# SCH_nfcCard_2025-11-06.net
KiCad netlist of a schematic drawn in EasyEDA
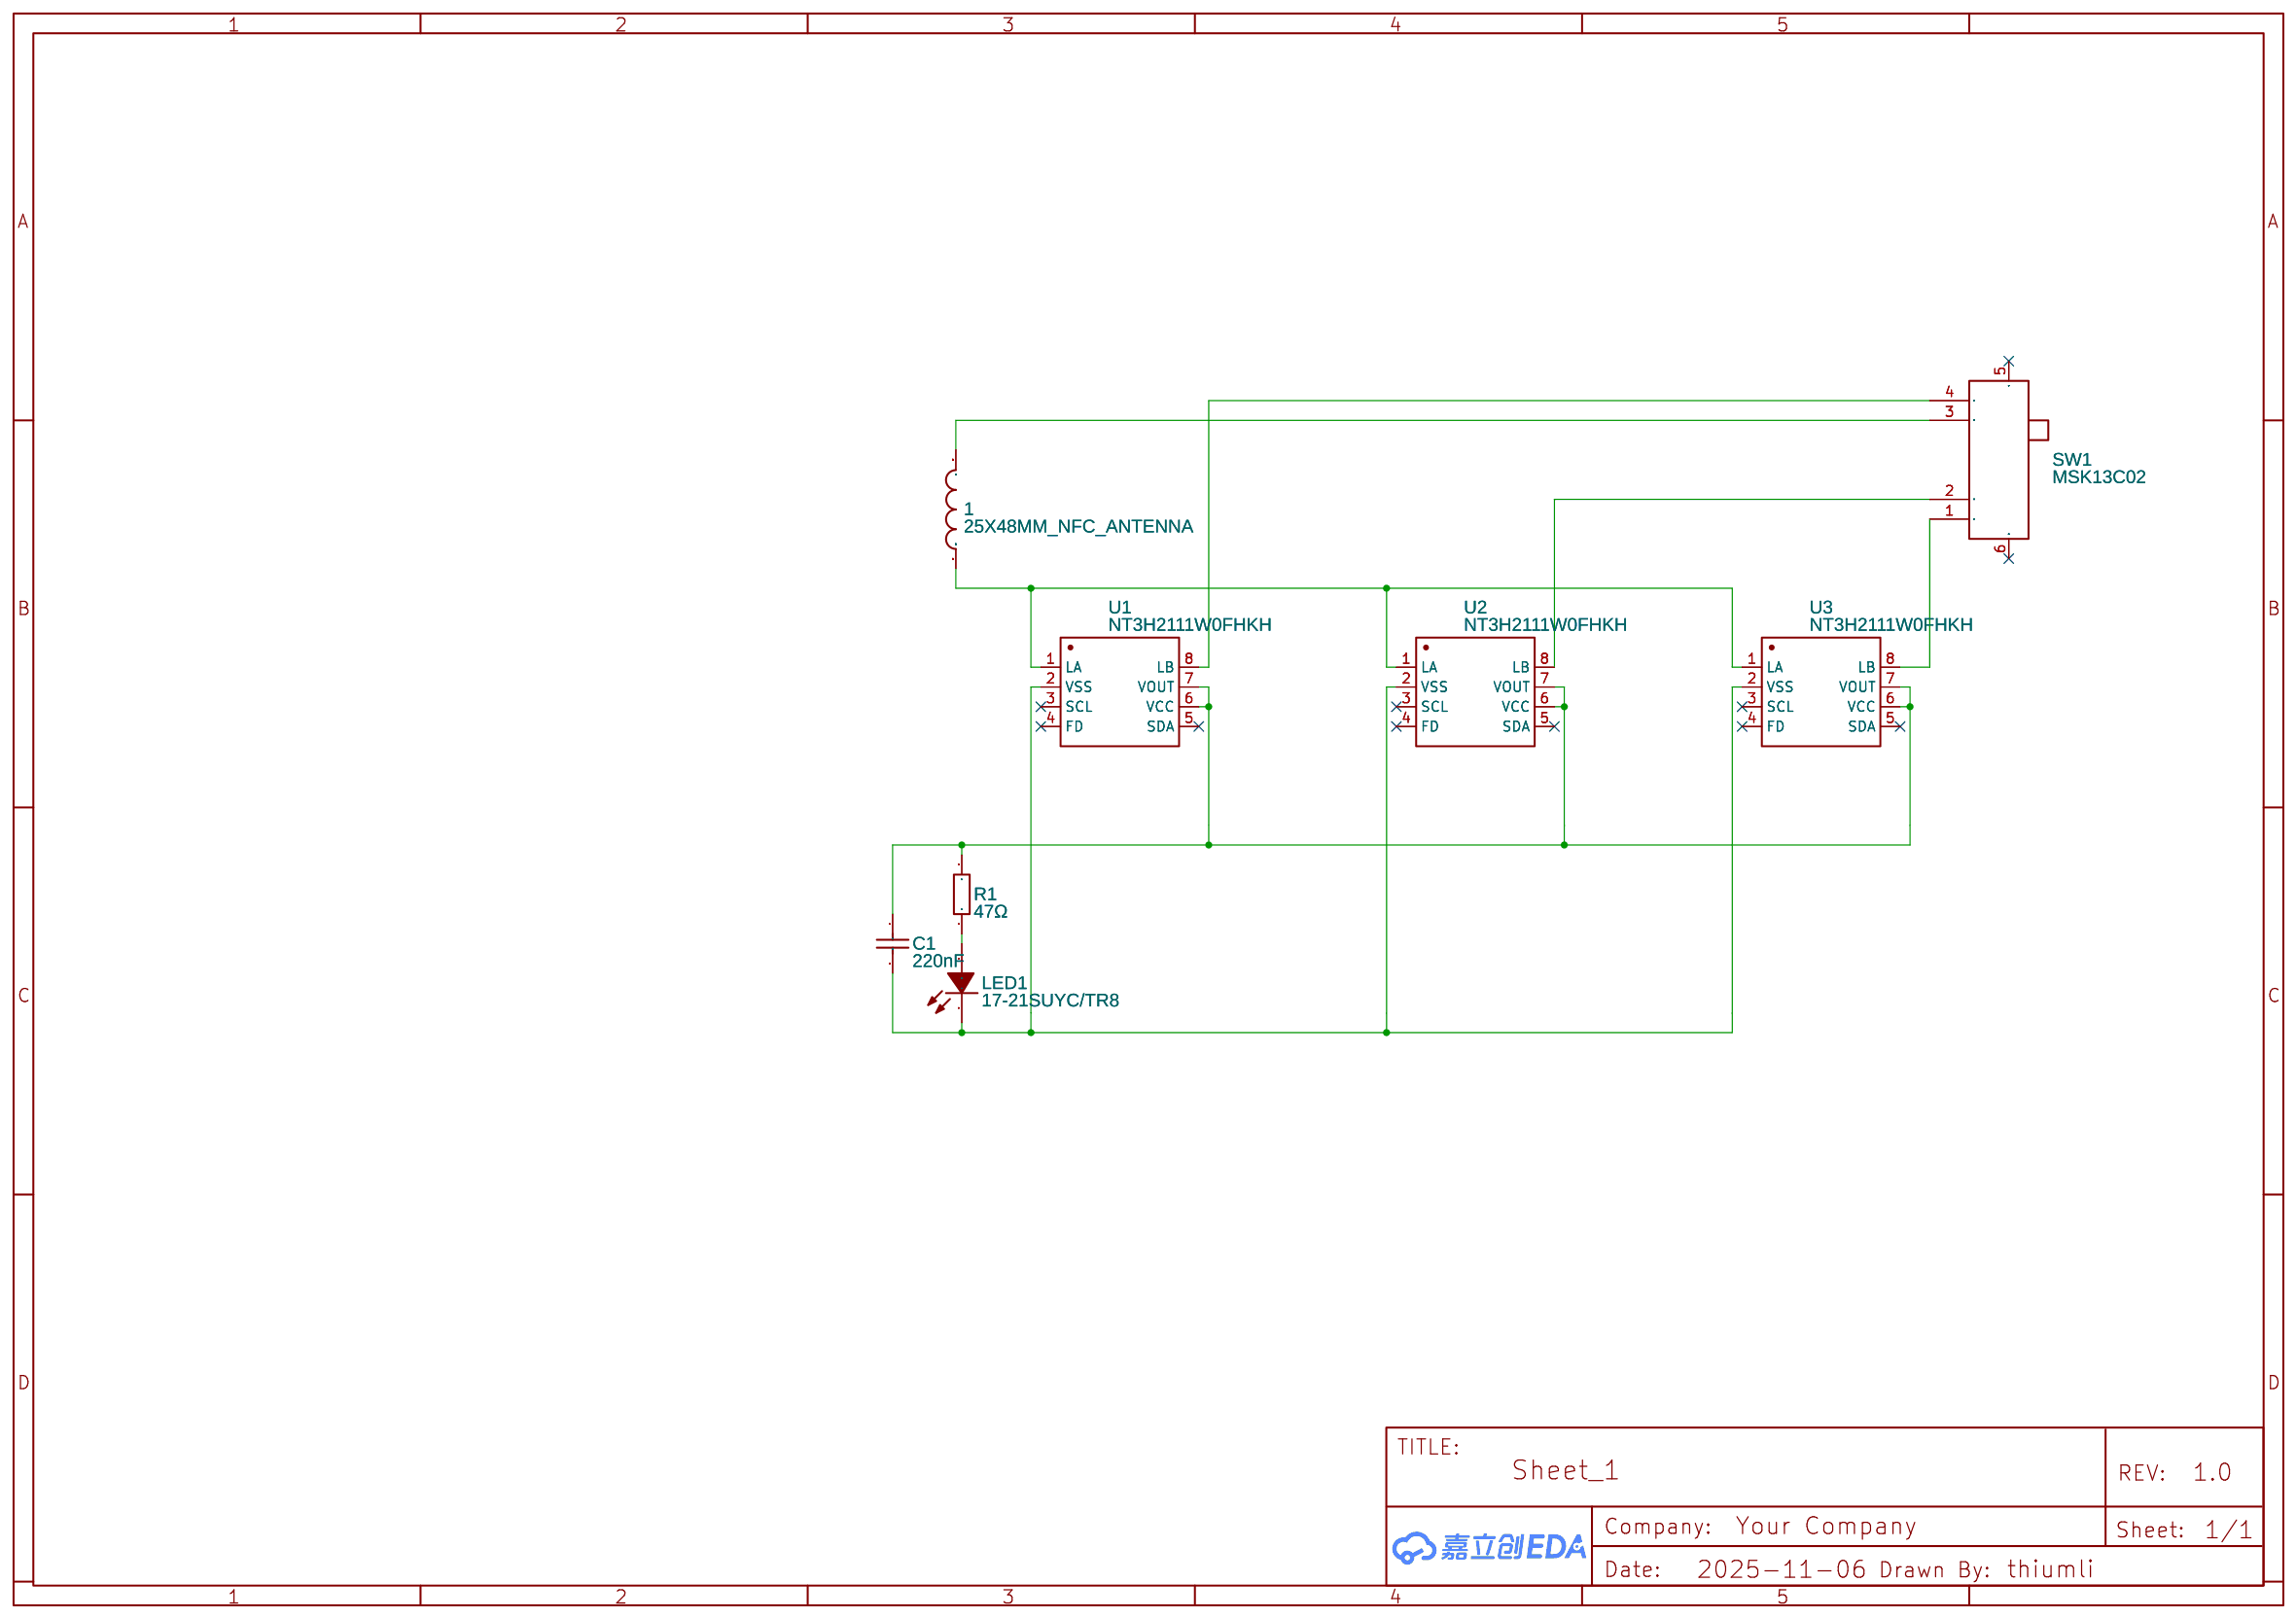
[diagram p0: schematic sheet]

(export (version "E")
  (design (tool "Eeschema 10.0.6"))
  (components
    (comp (ref "1") (value "25X48MM_NFC_ANTENNA") (libsource (lib "") (part "25X48MM_NFC_ANTENNA")))
    (comp (ref "C1")
      (value "220nF")
      (fields
        (field (name "Manufacturer Part") "CL10B224KA8NNNC")
        (field (name "Manufacturer") "SAMSUNG(三星)")
      )
      (libsource (lib "") (part "CL10B224KA8NNNC"))
    )
    (comp (ref "LED1")
      (value "17-21SUYC/TR8")
      (fields (field (name "Manufacturer Part") "KT-0805黄灯") (field (name "Manufacturer") "KENTO"))
      (libsource (lib "") (part "17-21SUYC/TR8"))
    )
    (comp (ref "R1")
      (value "47Ω")
      (fields
        (field (name "Manufacturer Part") "0603WAF470JT5E")
        (field (name "Manufacturer") "UNI-ROYAL(厚声)")
      )
      (libsource (lib "") (part "0603WAF470JT5E"))
    )
    (comp (ref "SW1")
      (value "MSK13C02")
      (fields (field (name "Manufacturer") "SHOU HAN(首韩)"))
      (libsource (lib "") (part "MSK13C02"))
    )
    (comp (ref "U1")
      (value "NT3H2111W0FHKH")
      (fields (field (name "Manufacturer") "NXP(恩智浦)"))
      (libsource (lib "") (part "NT3H2111W0FHKH"))
    )
    (comp (ref "U2")
      (value "NT3H2111W0FHKH")
      (fields (field (name "Manufacturer") "NXP(恩智浦)"))
      (libsource (lib "") (part "NT3H2111W0FHKH"))
    )
    (comp (ref "U3")
      (value "NT3H2111W0FHKH")
      (fields (field (name "Manufacturer") "NXP(恩智浦)"))
      (libsource (lib "") (part "NT3H2111W0FHKH"))
    )
  )
  (nets
    (net (code "1") (name "Net-(1-PadP$2)") (class "Default")
      (node (ref "1") (pin "P$2") (pinfunction "P$2_P$2") (pintype "bidirectional"))
      (node (ref "SW1") (pin "3") (pinfunction "3_3") (pintype "unspecified"))
    )
    (net (code "2") (name "Net-(LED1-+)") (class "Default")
      (node (ref "LED1") (pin "1") (pinfunction "+_1") (pintype "unspecified"))
      (node (ref "R1") (pin "1") (pinfunction "1_1") (pintype "input"))
    )
    (net (code "3") (name "Net-(LED1--)") (class "Default")
      (node (ref "C1") (pin "2") (pinfunction "2_2") (pintype "input"))
      (node (ref "LED1") (pin "2") (pinfunction "-_2") (pintype "unspecified"))
      (node (ref "U1") (pin "2") (pinfunction "VSS_2") (pintype "unspecified"))
      (node (ref "U2") (pin "2") (pinfunction "VSS_2") (pintype "unspecified"))
      (node (ref "U3") (pin "2") (pinfunction "VSS_2") (pintype "unspecified"))
    )
    (net (code "4") (name "Net-(U1-LA)") (class "Default")
      (node (ref "1") (pin "P$1") (pinfunction "P$1_P$1") (pintype "bidirectional"))
      (node (ref "U1") (pin "1") (pinfunction "LA_1") (pintype "unspecified"))
      (node (ref "U2") (pin "1") (pinfunction "LA_1") (pintype "unspecified"))
      (node (ref "U3") (pin "1") (pinfunction "LA_1") (pintype "unspecified"))
    )
    (net (code "5") (name "Net-(U1-LB)") (class "Default")
      (node (ref "SW1") (pin "4") (pinfunction "4_4") (pintype "unspecified"))
      (node (ref "U1") (pin "8") (pinfunction "LB_8") (pintype "unspecified"))
    )
    (net (code "6") (name "Net-(U1-VCC)") (class "Default")
      (node (ref "C1") (pin "1") (pinfunction "1_1") (pintype "input"))
      (node (ref "R1") (pin "2") (pinfunction "2_2") (pintype "input"))
      (node (ref "U1") (pin "6") (pinfunction "VCC_6") (pintype "unspecified"))
      (node (ref "U1") (pin "7") (pinfunction "VOUT_7") (pintype "unspecified"))
      (node (ref "U2") (pin "6") (pinfunction "VCC_6") (pintype "unspecified"))
      (node (ref "U2") (pin "7") (pinfunction "VOUT_7") (pintype "unspecified"))
      (node (ref "U3") (pin "6") (pinfunction "VCC_6") (pintype "unspecified"))
      (node (ref "U3") (pin "7") (pinfunction "VOUT_7") (pintype "unspecified"))
    )
    (net (code "7") (name "Net-(U2-LB)") (class "Default")
      (node (ref "SW1") (pin "2") (pinfunction "2_2") (pintype "unspecified"))
      (node (ref "U2") (pin "8") (pinfunction "LB_8") (pintype "unspecified"))
    )
    (net (code "8") (name "Net-(U3-LB)") (class "Default")
      (node (ref "SW1") (pin "1") (pinfunction "1_1") (pintype "unspecified"))
      (node (ref "U3") (pin "8") (pinfunction "LB_8") (pintype "unspecified"))
    )
    (net (code "9") (name "unconnected-(SW1-Pad5)") (class "Default")
      (node (ref "SW1") (pin "5") (pinfunction "5_5") (pintype "unspecified+no_connect"))
    )
    (net (code "10") (name "unconnected-(SW1-Pad6)") (class "Default")
      (node (ref "SW1") (pin "6") (pinfunction "6_6") (pintype "unspecified+no_connect"))
    )
    (net (code "11") (name "unconnected-(U1-FD-Pad4)") (class "Default")
      (node (ref "U1") (pin "4") (pinfunction "FD_4") (pintype "unspecified+no_connect"))
    )
    (net (code "12") (name "unconnected-(U1-SCL-Pad3)") (class "Default")
      (node (ref "U1") (pin "3") (pinfunction "SCL_3") (pintype "unspecified+no_connect"))
    )
    (net (code "13") (name "unconnected-(U1-SDA-Pad5)") (class "Default")
      (node (ref "U1") (pin "5") (pinfunction "SDA_5") (pintype "unspecified+no_connect"))
    )
    (net (code "14") (name "unconnected-(U2-FD-Pad4)") (class "Default")
      (node (ref "U2") (pin "4") (pinfunction "FD_4") (pintype "unspecified+no_connect"))
    )
    (net (code "15") (name "unconnected-(U2-SCL-Pad3)") (class "Default")
      (node (ref "U2") (pin "3") (pinfunction "SCL_3") (pintype "unspecified+no_connect"))
    )
    (net (code "16") (name "unconnected-(U2-SDA-Pad5)") (class "Default")
      (node (ref "U2") (pin "5") (pinfunction "SDA_5") (pintype "unspecified+no_connect"))
    )
    (net (code "17") (name "unconnected-(U3-FD-Pad4)") (class "Default")
      (node (ref "U3") (pin "4") (pinfunction "FD_4") (pintype "unspecified+no_connect"))
    )
    (net (code "18") (name "unconnected-(U3-SCL-Pad3)") (class "Default")
      (node (ref "U3") (pin "3") (pinfunction "SCL_3") (pintype "unspecified+no_connect"))
    )
    (net (code "19") (name "unconnected-(U3-SDA-Pad5)") (class "Default")
      (node (ref "U3") (pin "5") (pinfunction "SDA_5") (pintype "unspecified+no_connect"))
    )
  )
)
